# Master_Sheet1.net
KiCad netlist of a schematic drawn in Altium Designer
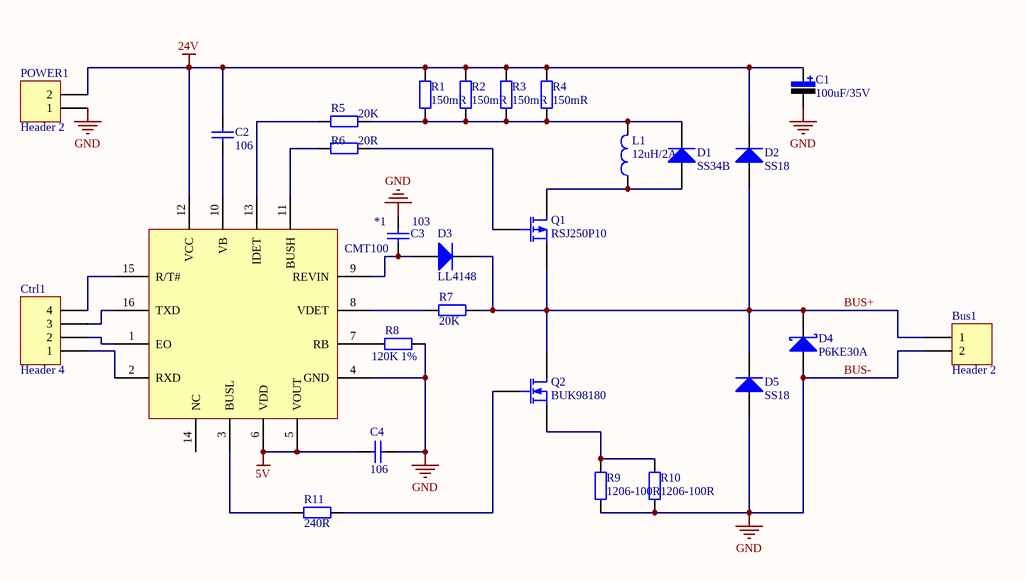
[diagram p0: Master_Sheet1.SchDoc]

(export (version "E")
  (design (tool "Eeschema 10.0.6"))
  (components
    (comp (ref "*1")
      (value "CMT100")
      (footprint "QFN-16")
      (description "主机")
      (libsource (lib "fszhang") (part "CMT100"))
    )
    (comp (ref "Bus1")
      (value "Header 2")
      (footprint "HDR1X2")
      (description "Header, 2-Pin")
      (fields (field (name "PUBLISHER") "Altium Limited"))
      (libsource (lib "") (part "Header 2_1"))
    )
    (comp (ref "C1")
      (value "100uF/35V")
      (footprint "C-RB-10")
      (description "极性电解电容")
      (fields (field (name "Comment") "Cap Pol") (field (name "PUBLISHER") "Altium Limited"))
      (libsource (lib "fszhang") (part "Cap Pol"))
    )
    (comp (ref "C2")
      (value "106")
      (footprint "C-RAD-0805")
      (description "无极性电容")
      (fields (field (name "Comment") "Cap") (field (name "PUBLISHER") "Altium Limited"))
      (libsource (lib "fszhang") (part "Cap"))
    )
    (comp (ref "C3")
      (value "103")
      (footprint "C-RAD-0805")
      (description "无极性电容")
      (fields (field (name "Comment") "Cap") (field (name "PUBLISHER") "Altium Limited"))
      (libsource (lib "fszhang") (part "Cap"))
    )
    (comp (ref "C4")
      (value "106")
      (footprint "C-RAD-0805")
      (description "无极性电容")
      (fields (field (name "Comment") "Cap") (field (name "PUBLISHER") "Altium Limited"))
      (libsource (lib "fszhang") (part "Cap"))
    )
    (comp (ref "Ctrl1")
      (value "Header 4")
      (footprint "HDR1X4")
      (description "Header, 4-Pin")
      (fields (field (name "PUBLISHER") "Altium Limited"))
      (libsource (lib "Miscellaneous Connectors") (part "Header 4"))
    )
    (comp (ref "D1")
      (value "SS34B")
      (footprint "DIODE-SMA")
      (description "Default Diode")
      (fields (field (name "PUBLISHER") "Altium Limited"))
      (libsource (lib "Miscellaneous Devices") (part "Diode"))
    )
    (comp (ref "D2")
      (value "SS18")
      (footprint "DIODE-SMA")
      (description "Default Diode")
      (fields (field (name "PUBLISHER") "Altium Limited"))
      (libsource (lib "Miscellaneous Devices") (part "Diode"))
    )
    (comp (ref "D3")
      (value "LL4148")
      (footprint "DO-35")
      (description "Default Diode")
      (fields (field (name "PUBLISHER") "Altium Limited"))
      (libsource (lib "Miscellaneous Devices") (part "Diode"))
    )
    (comp (ref "D4")
      (value "P6KE30A")
      (footprint "DO-15")
      (description "Schottky Rectifier")
      (fields (field (name "PUBLISHER") "Altium Limited"))
      (libsource (lib "Miscellaneous Devices") (part "Diode 18TQ045"))
    )
    (comp (ref "D5")
      (value "SS18")
      (footprint "DIODE-SMA")
      (description "Default Diode")
      (fields (field (name "PUBLISHER") "Altium Limited"))
      (libsource (lib "Miscellaneous Devices") (part "Diode"))
    )
    (comp (ref "L1")
      (value "12uH/2A")
      (footprint "L-RB-8")
      (description "电感")
      (fields (field (name "Comment") "Inductor") (field (name "PUBLISHER") "Altium Limited"))
      (libsource (lib "fszhang") (part "Inductor"))
    )
    (comp (ref "POWER1")
      (value "Header 2")
      (footprint "HDR1X2")
      (description "Header, 2-Pin")
      (fields (field (name "PUBLISHER") "Altium Limited"))
      (libsource (lib "Miscellaneous Connectors") (part "Header 2"))
    )
    (comp (ref "Q1")
      (value "RSJ250P10")
      (footprint "TO-220AB")
      (description "P-Channel MOSFET")
      (fields (field (name "PUBLISHER") "Altium Limited"))
      (libsource (lib "Miscellaneous Devices") (part "MOSFET-P"))
    )
    (comp (ref "Q2")
      (value "BUK98180")
      (footprint "TO-220AB")
      (description "N-Channel MOSFET")
      (fields (field (name "PUBLISHER") "Altium Limited"))
      (libsource (lib "Miscellaneous Devices") (part "MOSFET-N"))
    )
    (comp (ref "R1")
      (value "150mR")
      (footprint "0805-1")
      (description "贴片电阻")
      (fields (field (name "Comment") "Res1") (field (name "PUBLISHER") "Altium Limited"))
      (libsource (lib "fszhang") (part "Res1"))
    )
    (comp (ref "R2")
      (value "150mR")
      (footprint "0805-1")
      (description "贴片电阻")
      (fields (field (name "Comment") "Res1") (field (name "PUBLISHER") "Altium Limited"))
      (libsource (lib "fszhang") (part "Res1"))
    )
    (comp (ref "R3")
      (value "150mR")
      (footprint "0805-1")
      (description "贴片电阻")
      (fields (field (name "Comment") "Res1") (field (name "PUBLISHER") "Altium Limited"))
      (libsource (lib "fszhang") (part "Res1"))
    )
    (comp (ref "R4")
      (value "150mR")
      (footprint "0805-1")
      (description "贴片电阻")
      (fields (field (name "Comment") "Res1") (field (name "PUBLISHER") "Altium Limited"))
      (libsource (lib "fszhang") (part "Res1"))
    )
    (comp (ref "R5")
      (value "20K")
      (footprint "0805-1")
      (description "贴片电阻")
      (fields (field (name "Comment") "Res1") (field (name "PUBLISHER") "Altium Limited"))
      (libsource (lib "") (part "Res1_1"))
    )
    (comp (ref "R6")
      (value "20R")
      (footprint "0805-1")
      (description "贴片电阻")
      (fields (field (name "Comment") "Res1") (field (name "PUBLISHER") "Altium Limited"))
      (libsource (lib "") (part "Res1_1"))
    )
    (comp (ref "R7")
      (value "20K")
      (footprint "0805-1")
      (description "贴片电阻")
      (fields (field (name "Comment") "Res1") (field (name "PUBLISHER") "Altium Limited"))
      (libsource (lib "") (part "Res1_1"))
    )
    (comp (ref "R8")
      (value "120K 1%")
      (footprint "0805-1")
      (description "贴片电阻")
      (fields (field (name "Comment") "Res1") (field (name "PUBLISHER") "Altium Limited"))
      (libsource (lib "") (part "Res1_1"))
    )
    (comp (ref "R9")
      (value "1206-100R")
      (footprint "1206")
      (description "贴片电阻")
      (fields (field (name "Comment") "Res1") (field (name "PUBLISHER") "Altium Limited"))
      (libsource (lib "fszhang") (part "Res1"))
    )
    (comp (ref "R10")
      (value "1206-100R")
      (footprint "1206")
      (description "贴片电阻")
      (fields (field (name "Comment") "Res1") (field (name "PUBLISHER") "Altium Limited"))
      (libsource (lib "fszhang") (part "Res1"))
    )
    (comp (ref "R11")
      (value "240R")
      (footprint "0805-1")
      (description "贴片电阻")
      (fields (field (name "Comment") "Res1") (field (name "PUBLISHER") "Altium Limited"))
      (libsource (lib "") (part "Res1_1"))
    )
  )
  (nets
    (net (code "1") (name "/BUS+") (class "Default")
      (node (ref "Bus1") (pin "1") (pinfunction "1_1") (pintype "passive"))
      (node (ref "D2") (pin "1") (pinfunction "A_1") (pintype "passive"))
      (node (ref "D3") (pin "2") (pinfunction "K_2") (pintype "passive"))
      (node (ref "D4") (pin "1") (pinfunction "A_1") (pintype "passive"))
      (node (ref "D5") (pin "2") (pinfunction "K_2") (pintype "passive"))
      (node (ref "Q1") (pin "S") (pinfunction "S_S") (pintype "passive"))
      (node (ref "Q2") (pin "D") (pinfunction "D_D") (pintype "passive"))
      (node (ref "R7") (pin "2") (pinfunction "2_2") (pintype "passive"))
    )
    (net (code "2") (name "5V") (class "Default")
      (node (ref "*1") (pin "5") (pinfunction "VOUT_5") (pintype "passive"))
      (node (ref "*1") (pin "6") (pinfunction "VDD_6") (pintype "passive"))
      (node (ref "C4") (pin "1") (pinfunction "1_1") (pintype "passive"))
    )
    (net (code "3") (name "24V") (class "Default")
      (node (ref "*1") (pin "12") (pinfunction "VCC_12") (pintype "passive"))
      (node (ref "C1") (pin "1") (pinfunction "1_1") (pintype "passive"))
      (node (ref "C2") (pin "2") (pinfunction "2_2") (pintype "passive"))
      (node (ref "D2") (pin "2") (pinfunction "K_2") (pintype "passive"))
      (node (ref "POWER1") (pin "2") (pinfunction "2_2") (pintype "passive"))
      (node (ref "R1") (pin "2") (pinfunction "2_2") (pintype "passive"))
      (node (ref "R2") (pin "2") (pinfunction "2_2") (pintype "passive"))
      (node (ref "R3") (pin "2") (pinfunction "2_2") (pintype "passive"))
      (node (ref "R4") (pin "2") (pinfunction "2_2") (pintype "passive"))
    )
    (net (code "4") (name "GND") (class "Default")
      (node (ref "*1") (pin "4") (pinfunction "GND_4") (pintype "passive"))
      (node (ref "Bus1") (pin "2") (pinfunction "2_2") (pintype "passive"))
      (node (ref "C1") (pin "2") (pinfunction "2_2") (pintype "passive"))
      (node (ref "C3") (pin "2") (pinfunction "2_2") (pintype "passive"))
      (node (ref "C4") (pin "2") (pinfunction "2_2") (pintype "passive"))
      (node (ref "D4") (pin "2") (pinfunction "K_2") (pintype "passive"))
      (node (ref "D5") (pin "1") (pinfunction "A_1") (pintype "passive"))
      (node (ref "POWER1") (pin "1") (pinfunction "1_1") (pintype "passive"))
      (node (ref "R10") (pin "1") (pinfunction "1_1") (pintype "passive"))
      (node (ref "R8") (pin "2") (pinfunction "2_2") (pintype "passive"))
      (node (ref "R9") (pin "1") (pinfunction "1_1") (pintype "passive"))
    )
    (net (code "5") (name "Net-(*1-BUSH)") (class "Default")
      (node (ref "*1") (pin "11") (pinfunction "BUSH_11") (pintype "passive"))
      (node (ref "R6") (pin "1") (pinfunction "1_1") (pintype "passive"))
    )
    (net (code "6") (name "Net-(*1-BUSL)") (class "Default")
      (node (ref "*1") (pin "3") (pinfunction "BUSL_3") (pintype "passive"))
      (node (ref "R11") (pin "1") (pinfunction "1_1") (pintype "passive"))
    )
    (net (code "7") (name "Net-(*1-EO)") (class "Default")
      (node (ref "*1") (pin "1") (pinfunction "EO_1") (pintype "passive"))
      (node (ref "Ctrl1") (pin "2") (pinfunction "2_2") (pintype "passive"))
    )
    (net (code "8") (name "Net-(*1-IDET)") (class "Default")
      (node (ref "*1") (pin "13") (pinfunction "IDET_13") (pintype "passive"))
      (node (ref "R5") (pin "1") (pinfunction "1_1") (pintype "passive"))
    )
    (net (code "9") (name "Net-(*1-RB)") (class "Default")
      (node (ref "*1") (pin "7") (pinfunction "RB_7") (pintype "passive"))
      (node (ref "R8") (pin "1") (pinfunction "1_1") (pintype "passive"))
    )
    (net (code "10") (name "Net-(*1-REVIN)") (class "Default")
      (node (ref "*1") (pin "9") (pinfunction "REVIN_9") (pintype "passive"))
      (node (ref "C3") (pin "1") (pinfunction "1_1") (pintype "passive"))
      (node (ref "D3") (pin "1") (pinfunction "A_1") (pintype "passive"))
    )
    (net (code "11") (name "Net-(*1-RXD)") (class "Default")
      (node (ref "*1") (pin "2") (pinfunction "RXD_2") (pintype "passive"))
      (node (ref "Ctrl1") (pin "1") (pinfunction "1_1") (pintype "passive"))
    )
    (net (code "12") (name "Net-(*1-R{slash}T#)") (class "Default")
      (node (ref "*1") (pin "15") (pinfunction "R/T#_15") (pintype "passive"))
      (node (ref "Ctrl1") (pin "4") (pinfunction "4_4") (pintype "passive"))
    )
    (net (code "13") (name "Net-(*1-TXD)") (class "Default")
      (node (ref "*1") (pin "16") (pinfunction "TXD_16") (pintype "passive"))
      (node (ref "Ctrl1") (pin "3") (pinfunction "3_3") (pintype "passive"))
    )
    (net (code "14") (name "Net-(*1-VB)") (class "Default")
      (node (ref "*1") (pin "10") (pinfunction "VB_10") (pintype "passive"))
      (node (ref "C2") (pin "1") (pinfunction "1_1") (pintype "passive"))
    )
    (net (code "15") (name "Net-(*1-VDET)") (class "Default")
      (node (ref "*1") (pin "8") (pinfunction "VDET_8") (pintype "passive"))
      (node (ref "R7") (pin "1") (pinfunction "1_1") (pintype "passive"))
    )
    (net (code "16") (name "Net-(D1-A)") (class "Default")
      (node (ref "D1") (pin "1") (pinfunction "A_1") (pintype "passive"))
      (node (ref "L1") (pin "1") (pinfunction "1_1") (pintype "passive"))
      (node (ref "Q1") (pin "D") (pinfunction "D_D") (pintype "passive"))
    )
    (net (code "17") (name "Net-(D1-K)") (class "Default")
      (node (ref "D1") (pin "2") (pinfunction "K_2") (pintype "passive"))
      (node (ref "L1") (pin "2") (pinfunction "2_2") (pintype "passive"))
      (node (ref "R1") (pin "1") (pinfunction "1_1") (pintype "passive"))
      (node (ref "R2") (pin "1") (pinfunction "1_1") (pintype "passive"))
      (node (ref "R3") (pin "1") (pinfunction "1_1") (pintype "passive"))
      (node (ref "R4") (pin "1") (pinfunction "1_1") (pintype "passive"))
      (node (ref "R5") (pin "2") (pinfunction "2_2") (pintype "passive"))
    )
    (net (code "18") (name "Net-(Q1-PadG)") (class "Default")
      (node (ref "Q1") (pin "G") (pinfunction "G_G") (pintype "passive"))
      (node (ref "R6") (pin "2") (pinfunction "2_2") (pintype "passive"))
    )
    (net (code "19") (name "Net-(Q2-PadG)") (class "Default")
      (node (ref "Q2") (pin "G") (pinfunction "G_G") (pintype "passive"))
      (node (ref "R11") (pin "2") (pinfunction "2_2") (pintype "passive"))
    )
    (net (code "20") (name "Net-(Q2-PadS)") (class "Default")
      (node (ref "Q2") (pin "S") (pinfunction "S_S") (pintype "passive"))
      (node (ref "R10") (pin "2") (pinfunction "2_2") (pintype "passive"))
      (node (ref "R9") (pin "2") (pinfunction "2_2") (pintype "passive"))
    )
    (net (code "21") (name "unconnected-(*1-NC-Pad14)") (class "Default")
      (node (ref "*1") (pin "14") (pinfunction "NC_14") (pintype "passive"))
    )
  )
)
